# untitled.net
KiCad netlist of a schematic drawn in EAGLE
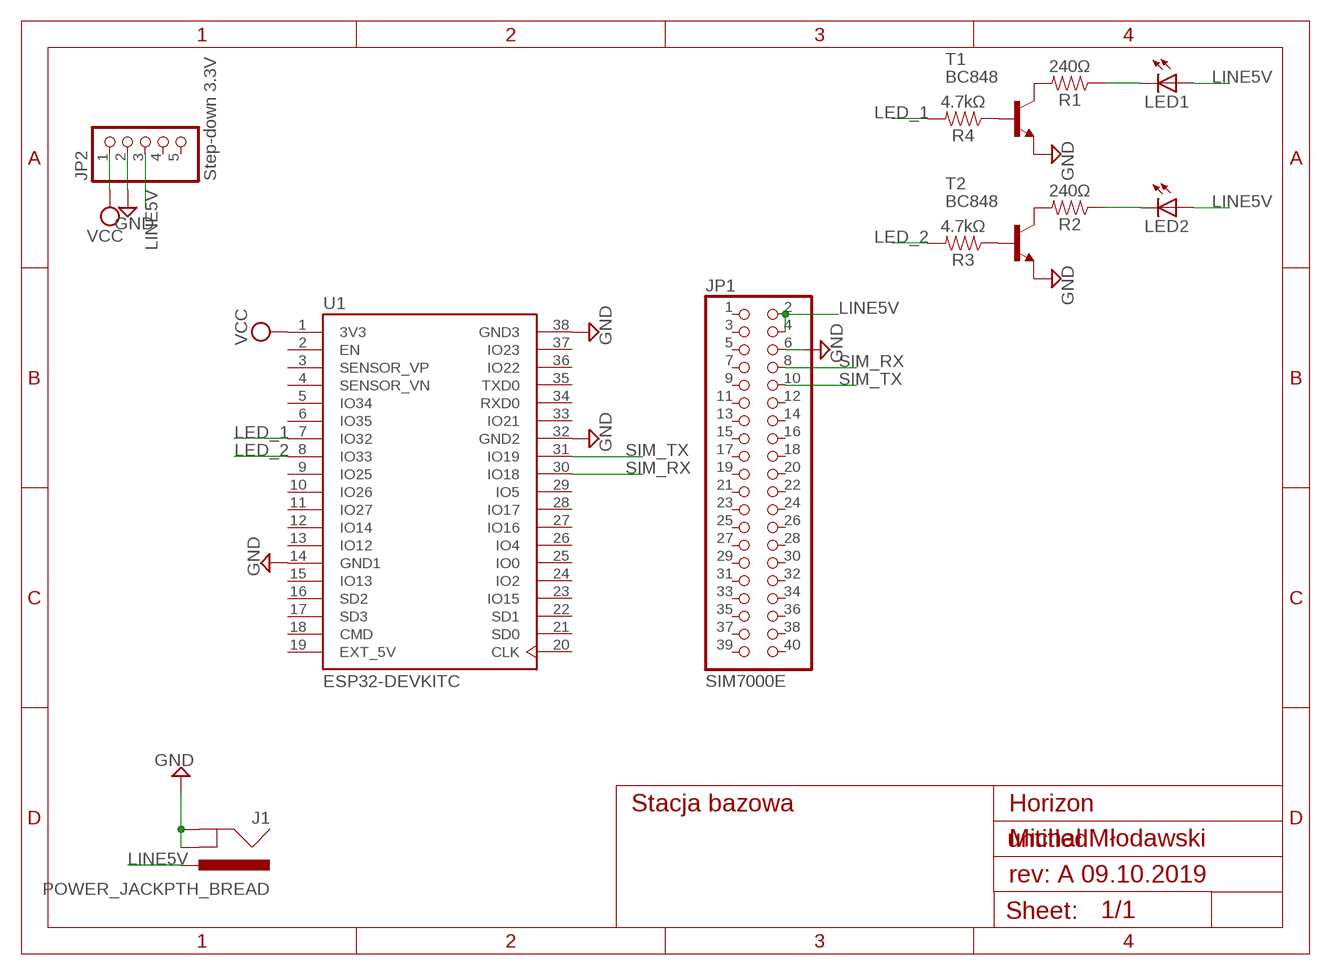
[diagram p0: schematic, sheet 1]

(export (version "E")
  (design (tool "Eeschema 10.0.6"))
  (components
    (comp (ref "J1")
      (value "POWER_JACKPTH_BREAD")
      (footprint "eagle-import:POWER_JACK_PTH_BREAD")
      (libsource (lib "eagle-import") (part "POWER_JACKPTH_BREAD"))
    )
    (comp (ref "JP1")
      (value "SIM7000E")
      (footprint "eagle-import:2X20")
      (libsource (lib "eagle-import") (part "PINHD-2X20"))
    )
    (comp (ref "JP2")
      (value "Step-down 3.3V")
      (footprint "eagle-import:1X05")
      (libsource (lib "eagle-import") (part "PINHD-1X5"))
    )
    (comp (ref "LED1")
      (value "LED5MM")
      (footprint "eagle-import:LED5MM")
      (libsource (lib "eagle-import") (part "LED5MM"))
    )
    (comp (ref "LED2")
      (value "LED5MM")
      (footprint "eagle-import:LED5MM")
      (libsource (lib "eagle-import") (part "LED5MM"))
    )
    (comp (ref "R1")
      (value "240Ω")
      (footprint "eagle-import:1206")
      (libsource (lib "eagle-import") (part "RESISTOR1206"))
    )
    (comp (ref "R2")
      (value "240Ω")
      (footprint "eagle-import:1206")
      (libsource (lib "eagle-import") (part "RESISTOR1206"))
    )
    (comp (ref "R3")
      (value "4.7kΩ")
      (footprint "eagle-import:1206")
      (libsource (lib "eagle-import") (part "RESISTOR1206"))
    )
    (comp (ref "R4")
      (value "4.7kΩ")
      (footprint "eagle-import:1206")
      (libsource (lib "eagle-import") (part "RESISTOR1206"))
    )
    (comp (ref "T1")
      (value "BC848")
      (footprint "eagle-import:SOT23")
      (libsource (lib "eagle-import") (part "BC848"))
    )
    (comp (ref "T2")
      (value "BC848")
      (footprint "eagle-import:SOT23")
      (libsource (lib "eagle-import") (part "BC848"))
    )
    (comp (ref "U1")
      (value "ESP32-DEVKITC")
      (footprint "eagle-import:MODULE_ESP32-DEVKITC")
      (fields (field (name "MF") "Espressif Systems") (field (name "MP") "ESP32-DEVKITC-32D-F"))
      (libsource (lib "eagle-import") (part "ESP32-DEVKITC"))
    )
  )
  (nets
    (net (code "1") (name "/EXT_5V") (class "Default")
      (node (ref "U1") (pin "19") (pinfunction "EXT_5V_19") (pintype "power_in"))
    )
    (net (code "2") (name "/LED_1") (class "Default")
      (node (ref "R4") (pin "2") (pinfunction "2_2") (pintype "passive"))
      (node (ref "U1") (pin "7") (pinfunction "IO32_7") (pintype "bidirectional"))
    )
    (net (code "3") (name "/LED_2") (class "Default")
      (node (ref "R3") (pin "2") (pinfunction "2_2") (pintype "passive"))
      (node (ref "U1") (pin "8") (pinfunction "IO33_8") (pintype "bidirectional"))
    )
    (net (code "4") (name "/LINE5V") (class "Default")
      (node (ref "J1") (pin "PWR") (pinfunction "PWR_PWR") (pintype "bidirectional"))
      (node (ref "JP1") (pin "2") (pinfunction "2_2") (pintype "passive"))
      (node (ref "JP1") (pin "4") (pinfunction "4_4") (pintype "passive"))
      (node (ref "JP2") (pin "3") (pinfunction "3_3") (pintype "passive"))
      (node (ref "LED1") (pin "A") (pinfunction "A_A") (pintype "passive"))
      (node (ref "LED2") (pin "A") (pinfunction "A_A") (pintype "passive"))
    )
    (net (code "5") (name "/SIM_RX") (class "Default")
      (node (ref "JP1") (pin "8") (pinfunction "8_8") (pintype "passive"))
      (node (ref "U1") (pin "30") (pinfunction "IO18_30") (pintype "bidirectional"))
    )
    (net (code "6") (name "/SIM_TX") (class "Default")
      (node (ref "JP1") (pin "10") (pinfunction "10_10") (pintype "passive"))
      (node (ref "U1") (pin "31") (pinfunction "IO19_31") (pintype "bidirectional"))
    )
    (net (code "7") (name "GND") (class "Default")
      (node (ref "J1") (pin "GND") (pinfunction "GND_GND") (pintype "bidirectional"))
      (node (ref "J1") (pin "GNDBREAK") (pinfunction "GNDBREAK_GNDBREAK") (pintype "bidirectional"))
      (node (ref "JP1") (pin "6") (pinfunction "6_6") (pintype "passive"))
      (node (ref "JP2") (pin "2") (pinfunction "2_2") (pintype "passive"))
      (node (ref "T1") (pin "2") (pinfunction "E_2") (pintype "passive"))
      (node (ref "T2") (pin "2") (pinfunction "E_2") (pintype "passive"))
      (node (ref "U1") (pin "14") (pinfunction "GND1_14") (pintype "power_in"))
      (node (ref "U1") (pin "32") (pinfunction "GND2_32") (pintype "power_in"))
      (node (ref "U1") (pin "38") (pinfunction "GND3_38") (pintype "power_in"))
    )
    (net (code "8") (name "Net-(LED1-C)") (class "Default")
      (node (ref "LED1") (pin "K") (pinfunction "C_K") (pintype "passive"))
      (node (ref "R1") (pin "1") (pinfunction "1_1") (pintype "passive"))
    )
    (net (code "9") (name "Net-(LED2-C)") (class "Default")
      (node (ref "LED2") (pin "K") (pinfunction "C_K") (pintype "passive"))
      (node (ref "R2") (pin "1") (pinfunction "1_1") (pintype "passive"))
    )
    (net (code "10") (name "Net-(T1-B)") (class "Default")
      (node (ref "R4") (pin "1") (pinfunction "1_1") (pintype "passive"))
      (node (ref "T1") (pin "1") (pinfunction "B_1") (pintype "passive"))
    )
    (net (code "11") (name "Net-(T1-C)") (class "Default")
      (node (ref "R1") (pin "2") (pinfunction "2_2") (pintype "passive"))
      (node (ref "T1") (pin "3") (pinfunction "C_3") (pintype "passive"))
    )
    (net (code "12") (name "Net-(T2-B)") (class "Default")
      (node (ref "R3") (pin "1") (pinfunction "1_1") (pintype "passive"))
      (node (ref "T2") (pin "1") (pinfunction "B_1") (pintype "passive"))
    )
    (net (code "13") (name "Net-(T2-C)") (class "Default")
      (node (ref "R2") (pin "2") (pinfunction "2_2") (pintype "passive"))
      (node (ref "T2") (pin "3") (pinfunction "C_3") (pintype "passive"))
    )
    (net (code "14") (name "VCC") (class "Default")
      (node (ref "JP2") (pin "1") (pinfunction "1_1") (pintype "passive"))
      (node (ref "U1") (pin "1") (pinfunction "3V3_1") (pintype "power_in"))
    )
    (net (code "15") (name "unconnected-(JP1-Pad1)") (class "Default")
      (node (ref "JP1") (pin "1") (pinfunction "1_1") (pintype "passive"))
    )
    (net (code "16") (name "unconnected-(JP1-Pad3)") (class "Default")
      (node (ref "JP1") (pin "3") (pinfunction "3_3") (pintype "passive"))
    )
    (net (code "17") (name "unconnected-(JP1-Pad5)") (class "Default")
      (node (ref "JP1") (pin "5") (pinfunction "5_5") (pintype "passive"))
    )
    (net (code "18") (name "unconnected-(JP1-Pad7)") (class "Default")
      (node (ref "JP1") (pin "7") (pinfunction "7_7") (pintype "passive"))
    )
    (net (code "19") (name "unconnected-(JP1-Pad9)") (class "Default")
      (node (ref "JP1") (pin "9") (pinfunction "9_9") (pintype "passive"))
    )
    (net (code "20") (name "unconnected-(JP1-Pad11)") (class "Default")
      (node (ref "JP1") (pin "11") (pinfunction "11_11") (pintype "passive"))
    )
    (net (code "21") (name "unconnected-(JP1-Pad12)") (class "Default")
      (node (ref "JP1") (pin "12") (pinfunction "12_12") (pintype "passive"))
    )
    (net (code "22") (name "unconnected-(JP1-Pad13)") (class "Default")
      (node (ref "JP1") (pin "13") (pinfunction "13_13") (pintype "passive"))
    )
    (net (code "23") (name "unconnected-(JP1-Pad14)") (class "Default")
      (node (ref "JP1") (pin "14") (pinfunction "14_14") (pintype "passive"))
    )
    (net (code "24") (name "unconnected-(JP1-Pad15)") (class "Default")
      (node (ref "JP1") (pin "15") (pinfunction "15_15") (pintype "passive"))
    )
    (net (code "25") (name "unconnected-(JP1-Pad16)") (class "Default")
      (node (ref "JP1") (pin "16") (pinfunction "16_16") (pintype "passive"))
    )
    (net (code "26") (name "unconnected-(JP1-Pad17)") (class "Default")
      (node (ref "JP1") (pin "17") (pinfunction "17_17") (pintype "passive"))
    )
    (net (code "27") (name "unconnected-(JP1-Pad18)") (class "Default")
      (node (ref "JP1") (pin "18") (pinfunction "18_18") (pintype "passive"))
    )
    (net (code "28") (name "unconnected-(JP1-Pad19)") (class "Default")
      (node (ref "JP1") (pin "19") (pinfunction "19_19") (pintype "passive"))
    )
    (net (code "29") (name "unconnected-(JP1-Pad20)") (class "Default")
      (node (ref "JP1") (pin "20") (pinfunction "20_20") (pintype "passive"))
    )
    (net (code "30") (name "unconnected-(JP1-Pad21)") (class "Default")
      (node (ref "JP1") (pin "21") (pinfunction "21_21") (pintype "passive"))
    )
    (net (code "31") (name "unconnected-(JP1-Pad22)") (class "Default")
      (node (ref "JP1") (pin "22") (pinfunction "22_22") (pintype "passive"))
    )
    (net (code "32") (name "unconnected-(JP1-Pad23)") (class "Default")
      (node (ref "JP1") (pin "23") (pinfunction "23_23") (pintype "passive"))
    )
    (net (code "33") (name "unconnected-(JP1-Pad24)") (class "Default")
      (node (ref "JP1") (pin "24") (pinfunction "24_24") (pintype "passive"))
    )
    (net (code "34") (name "unconnected-(JP1-Pad25)") (class "Default")
      (node (ref "JP1") (pin "25") (pinfunction "25_25") (pintype "passive"))
    )
    (net (code "35") (name "unconnected-(JP1-Pad26)") (class "Default")
      (node (ref "JP1") (pin "26") (pinfunction "26_26") (pintype "passive"))
    )
    (net (code "36") (name "unconnected-(JP1-Pad27)") (class "Default")
      (node (ref "JP1") (pin "27") (pinfunction "27_27") (pintype "passive"))
    )
    (net (code "37") (name "unconnected-(JP1-Pad28)") (class "Default")
      (node (ref "JP1") (pin "28") (pinfunction "28_28") (pintype "passive"))
    )
    (net (code "38") (name "unconnected-(JP1-Pad29)") (class "Default")
      (node (ref "JP1") (pin "29") (pinfunction "29_29") (pintype "passive"))
    )
    (net (code "39") (name "unconnected-(JP1-Pad30)") (class "Default")
      (node (ref "JP1") (pin "30") (pinfunction "30_30") (pintype "passive"))
    )
    (net (code "40") (name "unconnected-(JP1-Pad31)") (class "Default")
      (node (ref "JP1") (pin "31") (pinfunction "31_31") (pintype "passive"))
    )
    (net (code "41") (name "unconnected-(JP1-Pad32)") (class "Default")
      (node (ref "JP1") (pin "32") (pinfunction "32_32") (pintype "passive"))
    )
    (net (code "42") (name "unconnected-(JP1-Pad33)") (class "Default")
      (node (ref "JP1") (pin "33") (pinfunction "33_33") (pintype "passive"))
    )
    (net (code "43") (name "unconnected-(JP1-Pad34)") (class "Default")
      (node (ref "JP1") (pin "34") (pinfunction "34_34") (pintype "passive"))
    )
    (net (code "44") (name "unconnected-(JP1-Pad35)") (class "Default")
      (node (ref "JP1") (pin "35") (pinfunction "35_35") (pintype "passive"))
    )
    (net (code "45") (name "unconnected-(JP1-Pad36)") (class "Default")
      (node (ref "JP1") (pin "36") (pinfunction "36_36") (pintype "passive"))
    )
    (net (code "46") (name "unconnected-(JP1-Pad37)") (class "Default")
      (node (ref "JP1") (pin "37") (pinfunction "37_37") (pintype "passive"))
    )
    (net (code "47") (name "unconnected-(JP1-Pad38)") (class "Default")
      (node (ref "JP1") (pin "38") (pinfunction "38_38") (pintype "passive"))
    )
    (net (code "48") (name "unconnected-(JP1-Pad39)") (class "Default")
      (node (ref "JP1") (pin "39") (pinfunction "39_39") (pintype "passive"))
    )
    (net (code "49") (name "unconnected-(JP1-Pad40)") (class "Default")
      (node (ref "JP1") (pin "40") (pinfunction "40_40") (pintype "passive"))
    )
    (net (code "50") (name "unconnected-(JP2-Pad4)") (class "Default")
      (node (ref "JP2") (pin "4") (pinfunction "4_4") (pintype "passive"))
    )
    (net (code "51") (name "unconnected-(JP2-Pad5)") (class "Default")
      (node (ref "JP2") (pin "5") (pinfunction "5_5") (pintype "passive"))
    )
    (net (code "52") (name "unconnected-(U1-CLK-Pad20)") (class "Default")
      (node (ref "U1") (pin "20") (pinfunction "CLK_20") (pintype "input"))
    )
    (net (code "53") (name "unconnected-(U1-CMD-Pad18)") (class "Default")
      (node (ref "U1") (pin "18") (pinfunction "CMD_18") (pintype "bidirectional"))
    )
    (net (code "54") (name "unconnected-(U1-EN-Pad2)") (class "Default")
      (node (ref "U1") (pin "2") (pinfunction "EN_2") (pintype "input"))
    )
    (net (code "55") (name "unconnected-(U1-IO0-Pad25)") (class "Default")
      (node (ref "U1") (pin "25") (pinfunction "IO0_25") (pintype "bidirectional"))
    )
    (net (code "56") (name "unconnected-(U1-IO2-Pad24)") (class "Default")
      (node (ref "U1") (pin "24") (pinfunction "IO2_24") (pintype "bidirectional"))
    )
    (net (code "57") (name "unconnected-(U1-IO4-Pad26)") (class "Default")
      (node (ref "U1") (pin "26") (pinfunction "IO4_26") (pintype "bidirectional"))
    )
    (net (code "58") (name "unconnected-(U1-IO5-Pad29)") (class "Default")
      (node (ref "U1") (pin "29") (pinfunction "IO5_29") (pintype "bidirectional"))
    )
    (net (code "59") (name "unconnected-(U1-IO12-Pad13)") (class "Default")
      (node (ref "U1") (pin "13") (pinfunction "IO12_13") (pintype "bidirectional"))
    )
    (net (code "60") (name "unconnected-(U1-IO13-Pad15)") (class "Default")
      (node (ref "U1") (pin "15") (pinfunction "IO13_15") (pintype "bidirectional"))
    )
    (net (code "61") (name "unconnected-(U1-IO14-Pad12)") (class "Default")
      (node (ref "U1") (pin "12") (pinfunction "IO14_12") (pintype "bidirectional"))
    )
    (net (code "62") (name "unconnected-(U1-IO15-Pad23)") (class "Default")
      (node (ref "U1") (pin "23") (pinfunction "IO15_23") (pintype "bidirectional"))
    )
    (net (code "63") (name "unconnected-(U1-IO16-Pad27)") (class "Default")
      (node (ref "U1") (pin "27") (pinfunction "IO16_27") (pintype "bidirectional"))
    )
    (net (code "64") (name "unconnected-(U1-IO17-Pad28)") (class "Default")
      (node (ref "U1") (pin "28") (pinfunction "IO17_28") (pintype "bidirectional"))
    )
    (net (code "65") (name "unconnected-(U1-IO21-Pad33)") (class "Default")
      (node (ref "U1") (pin "33") (pinfunction "IO21_33") (pintype "bidirectional"))
    )
    (net (code "66") (name "unconnected-(U1-IO22-Pad36)") (class "Default")
      (node (ref "U1") (pin "36") (pinfunction "IO22_36") (pintype "bidirectional"))
    )
    (net (code "67") (name "unconnected-(U1-IO23-Pad37)") (class "Default")
      (node (ref "U1") (pin "37") (pinfunction "IO23_37") (pintype "bidirectional"))
    )
    (net (code "68") (name "unconnected-(U1-IO25-Pad9)") (class "Default")
      (node (ref "U1") (pin "9") (pinfunction "IO25_9") (pintype "bidirectional"))
    )
    (net (code "69") (name "unconnected-(U1-IO26-Pad10)") (class "Default")
      (node (ref "U1") (pin "10") (pinfunction "IO26_10") (pintype "bidirectional"))
    )
    (net (code "70") (name "unconnected-(U1-IO27-Pad11)") (class "Default")
      (node (ref "U1") (pin "11") (pinfunction "IO27_11") (pintype "bidirectional"))
    )
    (net (code "71") (name "unconnected-(U1-IO34-Pad5)") (class "Default")
      (node (ref "U1") (pin "5") (pinfunction "IO34_5") (pintype "bidirectional"))
    )
    (net (code "72") (name "unconnected-(U1-IO35-Pad6)") (class "Default")
      (node (ref "U1") (pin "6") (pinfunction "IO35_6") (pintype "bidirectional"))
    )
    (net (code "73") (name "unconnected-(U1-RXD0-Pad34)") (class "Default")
      (node (ref "U1") (pin "34") (pinfunction "RXD0_34") (pintype "input"))
    )
    (net (code "74") (name "unconnected-(U1-SD0-Pad21)") (class "Default")
      (node (ref "U1") (pin "21") (pinfunction "SD0_21") (pintype "bidirectional"))
    )
    (net (code "75") (name "unconnected-(U1-SD1-Pad22)") (class "Default")
      (node (ref "U1") (pin "22") (pinfunction "SD1_22") (pintype "bidirectional"))
    )
    (net (code "76") (name "unconnected-(U1-SD2-Pad16)") (class "Default")
      (node (ref "U1") (pin "16") (pinfunction "SD2_16") (pintype "bidirectional"))
    )
    (net (code "77") (name "unconnected-(U1-SD3-Pad17)") (class "Default")
      (node (ref "U1") (pin "17") (pinfunction "SD3_17") (pintype "bidirectional"))
    )
    (net (code "78") (name "unconnected-(U1-SENSOR_VN-Pad4)") (class "Default")
      (node (ref "U1") (pin "4") (pinfunction "SENSOR_VN_4") (pintype "input"))
    )
    (net (code "79") (name "unconnected-(U1-SENSOR_VP-Pad3)") (class "Default")
      (node (ref "U1") (pin "3") (pinfunction "SENSOR_VP_3") (pintype "input"))
    )
    (net (code "80") (name "unconnected-(U1-TXD0-Pad35)") (class "Default")
      (node (ref "U1") (pin "35") (pinfunction "TXD0_35") (pintype "output"))
    )
  )
)
